# board.net
KiCad netlist of a schematic drawn in EAGLE
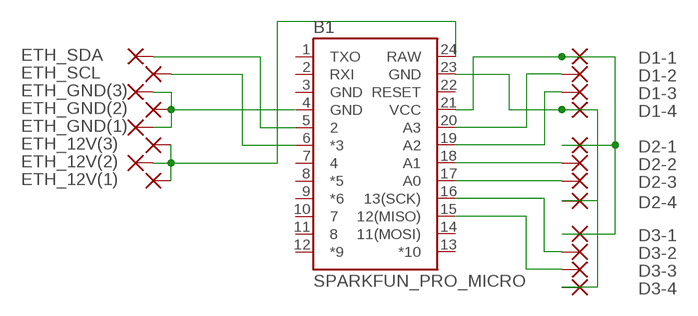
[diagram p0: schematic, sheet 1]

(export (version "E")
  (design (tool "Eeschema 10.0.6"))
  (components
    (comp (ref "B1")
      (value "SPARKFUN_PRO_MICRO")
      (footprint "eagle-import:SPARKFUN_PRO_MICRO")
      (libsource (lib "eagle-import") (part "SPARKFUN_PRO_MICRO"))
    )
    (comp (ref "D1-1")
      (value "2,15/1,0")
      (footprint "eagle-import:2,15_1,0")
      (libsource (lib "eagle-import") (part "2,15/1,0"))
    )
    (comp (ref "D1-2")
      (value "2,15/1,0")
      (footprint "eagle-import:2,15_1,0")
      (libsource (lib "eagle-import") (part "2,15/1,0"))
    )
    (comp (ref "D1-3")
      (value "2,15/1,0")
      (footprint "eagle-import:2,15_1,0")
      (libsource (lib "eagle-import") (part "2,15/1,0"))
    )
    (comp (ref "D1-4")
      (value "2,15/1,0")
      (footprint "eagle-import:2,15_1,0")
      (libsource (lib "eagle-import") (part "2,15/1,0"))
    )
    (comp (ref "D2-1")
      (value "2,15/1,0")
      (footprint "eagle-import:2,15_1,0")
      (libsource (lib "eagle-import") (part "2,15/1,0"))
    )
    (comp (ref "D2-2")
      (value "2,15/1,0")
      (footprint "eagle-import:2,15_1,0")
      (libsource (lib "eagle-import") (part "2,15/1,0"))
    )
    (comp (ref "D2-3")
      (value "2,15/1,0")
      (footprint "eagle-import:2,15_1,0")
      (libsource (lib "eagle-import") (part "2,15/1,0"))
    )
    (comp (ref "D2-4")
      (value "2,15/1,0")
      (footprint "eagle-import:2,15_1,0")
      (libsource (lib "eagle-import") (part "2,15/1,0"))
    )
    (comp (ref "D3-1")
      (value "2,15/1,0")
      (footprint "eagle-import:2,15_1,0")
      (libsource (lib "eagle-import") (part "2,15/1,0"))
    )
    (comp (ref "D3-2")
      (value "2,15/1,0")
      (footprint "eagle-import:2,15_1,0")
      (libsource (lib "eagle-import") (part "2,15/1,0"))
    )
    (comp (ref "D3-3")
      (value "2,15/1,0")
      (footprint "eagle-import:2,15_1,0")
      (libsource (lib "eagle-import") (part "2,15/1,0"))
    )
    (comp (ref "D3-4")
      (value "2,15/1,0")
      (footprint "eagle-import:2,15_1,0")
      (libsource (lib "eagle-import") (part "2,15/1,0"))
    )
    (comp (ref "ETH_12V(1)")
      (value "2,15/1,0")
      (footprint "eagle-import:2,15_1,0")
      (libsource (lib "eagle-import") (part "2,15/1,0"))
    )
    (comp (ref "ETH_12V(2)")
      (value "2,15/1,0")
      (footprint "eagle-import:2,15_1,0")
      (libsource (lib "eagle-import") (part "2,15/1,0"))
    )
    (comp (ref "ETH_12V(3)")
      (value "2,15/1,0")
      (footprint "eagle-import:2,15_1,0")
      (libsource (lib "eagle-import") (part "2,15/1,0"))
    )
    (comp (ref "ETH_GND(1)")
      (value "2,15/1,0")
      (footprint "eagle-import:2,15_1,0")
      (libsource (lib "eagle-import") (part "2,15/1,0"))
    )
    (comp (ref "ETH_GND(2)")
      (value "2,15/1,0")
      (footprint "eagle-import:2,15_1,0")
      (libsource (lib "eagle-import") (part "2,15/1,0"))
    )
    (comp (ref "ETH_GND(3)")
      (value "2,15/1,0")
      (footprint "eagle-import:2,15_1,0")
      (libsource (lib "eagle-import") (part "2,15/1,0"))
    )
    (comp (ref "ETH_SCL")
      (value "2,15/1,0")
      (footprint "eagle-import:2,15_1,0")
      (libsource (lib "eagle-import") (part "2,15/1,0"))
    )
    (comp (ref "ETH_SDA")
      (value "2,15/1,0")
      (footprint "eagle-import:2,15_1,0")
      (libsource (lib "eagle-import") (part "2,15/1,0"))
    )
  )
  (nets
    (net (code "1") (name "/GND") (class "Default")
      (node (ref "B1") (pin "3") (pinfunction "GND_3") (pintype "power_in"))
    )
    (net (code "2") (name "Net-(B1-*3)") (class "Default")
      (node (ref "B1") (pin "6") (pinfunction "*3_6") (pintype "bidirectional"))
      (node (ref "ETH_SCL") (pin "1") (pinfunction "P_1") (pintype "passive"))
    )
    (net (code "3") (name "Net-(B1-2)") (class "Default")
      (node (ref "B1") (pin "5") (pinfunction "2_5") (pintype "bidirectional"))
      (node (ref "ETH_SDA") (pin "1") (pinfunction "P_1") (pintype "passive"))
    )
    (net (code "4") (name "Net-(B1-12(MISO))") (class "Default")
      (node (ref "B1") (pin "15") (pinfunction "12(MISO)_15") (pintype "bidirectional"))
      (node (ref "D3-3") (pin "1") (pinfunction "P_1") (pintype "passive"))
    )
    (net (code "5") (name "Net-(B1-13(SCK))") (class "Default")
      (node (ref "B1") (pin "16") (pinfunction "13(SCK)_16") (pintype "bidirectional"))
      (node (ref "D3-2") (pin "1") (pinfunction "P_1") (pintype "passive"))
    )
    (net (code "6") (name "Net-(B1-A0)") (class "Default")
      (node (ref "B1") (pin "17") (pinfunction "A0_17") (pintype "bidirectional"))
      (node (ref "D2-3") (pin "1") (pinfunction "P_1") (pintype "passive"))
    )
    (net (code "7") (name "Net-(B1-A1)") (class "Default")
      (node (ref "B1") (pin "18") (pinfunction "A1_18") (pintype "bidirectional"))
      (node (ref "D2-2") (pin "1") (pinfunction "P_1") (pintype "passive"))
    )
    (net (code "8") (name "Net-(B1-A2)") (class "Default")
      (node (ref "B1") (pin "19") (pinfunction "A2_19") (pintype "bidirectional"))
      (node (ref "D1-3") (pin "1") (pinfunction "P_1") (pintype "passive"))
    )
    (net (code "9") (name "Net-(B1-A3)") (class "Default")
      (node (ref "B1") (pin "20") (pinfunction "A3_20") (pintype "bidirectional"))
      (node (ref "D1-2") (pin "1") (pinfunction "P_1") (pintype "passive"))
    )
    (net (code "10") (name "Net-(B1-RAW)") (class "Default")
      (node (ref "B1") (pin "24") (pinfunction "RAW_24") (pintype "power_in"))
      (node (ref "ETH_12V(1)") (pin "1") (pinfunction "P_1") (pintype "passive"))
      (node (ref "ETH_12V(2)") (pin "1") (pinfunction "P_1") (pintype "passive"))
      (node (ref "ETH_12V(3)") (pin "1") (pinfunction "P_1") (pintype "passive"))
    )
    (net (code "11") (name "Net-(B1-VCC)") (class "Default")
      (node (ref "B1") (pin "21") (pinfunction "VCC_21") (pintype "power_in"))
      (node (ref "D1-1") (pin "1") (pinfunction "P_1") (pintype "passive"))
      (node (ref "D2-1") (pin "1") (pinfunction "P_1") (pintype "passive"))
      (node (ref "D3-1") (pin "1") (pinfunction "P_1") (pintype "passive"))
    )
    (net (code "12") (name "Net-(D1-4-P)") (class "Default")
      (node (ref "B1") (pin "23") (pinfunction "GND_23") (pintype "power_in"))
      (node (ref "D1-4") (pin "1") (pinfunction "P_1") (pintype "passive"))
      (node (ref "D2-4") (pin "1") (pinfunction "P_1") (pintype "passive"))
      (node (ref "D3-4") (pin "1") (pinfunction "P_1") (pintype "passive"))
    )
    (net (code "13") (name "Net-(ETH_GND(1)-P)") (class "Default")
      (node (ref "B1") (pin "4") (pinfunction "GND_4") (pintype "power_in"))
      (node (ref "ETH_GND(1)") (pin "1") (pinfunction "P_1") (pintype "passive"))
      (node (ref "ETH_GND(2)") (pin "1") (pinfunction "P_1") (pintype "passive"))
      (node (ref "ETH_GND(3)") (pin "1") (pinfunction "P_1") (pintype "passive"))
    )
    (net (code "14") (name "unconnected-(B1-*5-Pad8)") (class "Default")
      (node (ref "B1") (pin "8") (pinfunction "*5_8") (pintype "bidirectional"))
    )
    (net (code "15") (name "unconnected-(B1-*6-Pad9)") (class "Default")
      (node (ref "B1") (pin "9") (pinfunction "*6_9") (pintype "bidirectional"))
    )
    (net (code "16") (name "unconnected-(B1-*9-Pad12)") (class "Default")
      (node (ref "B1") (pin "12") (pinfunction "*9_12") (pintype "bidirectional"))
    )
    (net (code "17") (name "unconnected-(B1-*10-Pad13)") (class "Default")
      (node (ref "B1") (pin "13") (pinfunction "*10_13") (pintype "bidirectional"))
    )
    (net (code "18") (name "unconnected-(B1-4-Pad7)") (class "Default")
      (node (ref "B1") (pin "7") (pinfunction "4_7") (pintype "bidirectional"))
    )
    (net (code "19") (name "unconnected-(B1-7-Pad10)") (class "Default")
      (node (ref "B1") (pin "10") (pinfunction "7_10") (pintype "bidirectional"))
    )
    (net (code "20") (name "unconnected-(B1-8-Pad11)") (class "Default")
      (node (ref "B1") (pin "11") (pinfunction "8_11") (pintype "bidirectional"))
    )
    (net (code "21") (name "unconnected-(B1-11(MOSI)-Pad14)") (class "Default")
      (node (ref "B1") (pin "14") (pinfunction "11(MOSI)_14") (pintype "bidirectional"))
    )
    (net (code "22") (name "unconnected-(B1-RESET-Pad22)") (class "Default")
      (node (ref "B1") (pin "22") (pinfunction "RESET_22") (pintype "bidirectional"))
    )
    (net (code "23") (name "unconnected-(B1-RXI-Pad2)") (class "Default")
      (node (ref "B1") (pin "2") (pinfunction "RXI_2") (pintype "bidirectional"))
    )
    (net (code "24") (name "unconnected-(B1-TXO-Pad1)") (class "Default")
      (node (ref "B1") (pin "1") (pinfunction "TXO_1") (pintype "bidirectional"))
    )
  )
)
